# newboard.net
KiCad netlist of a schematic drawn in EAGLE
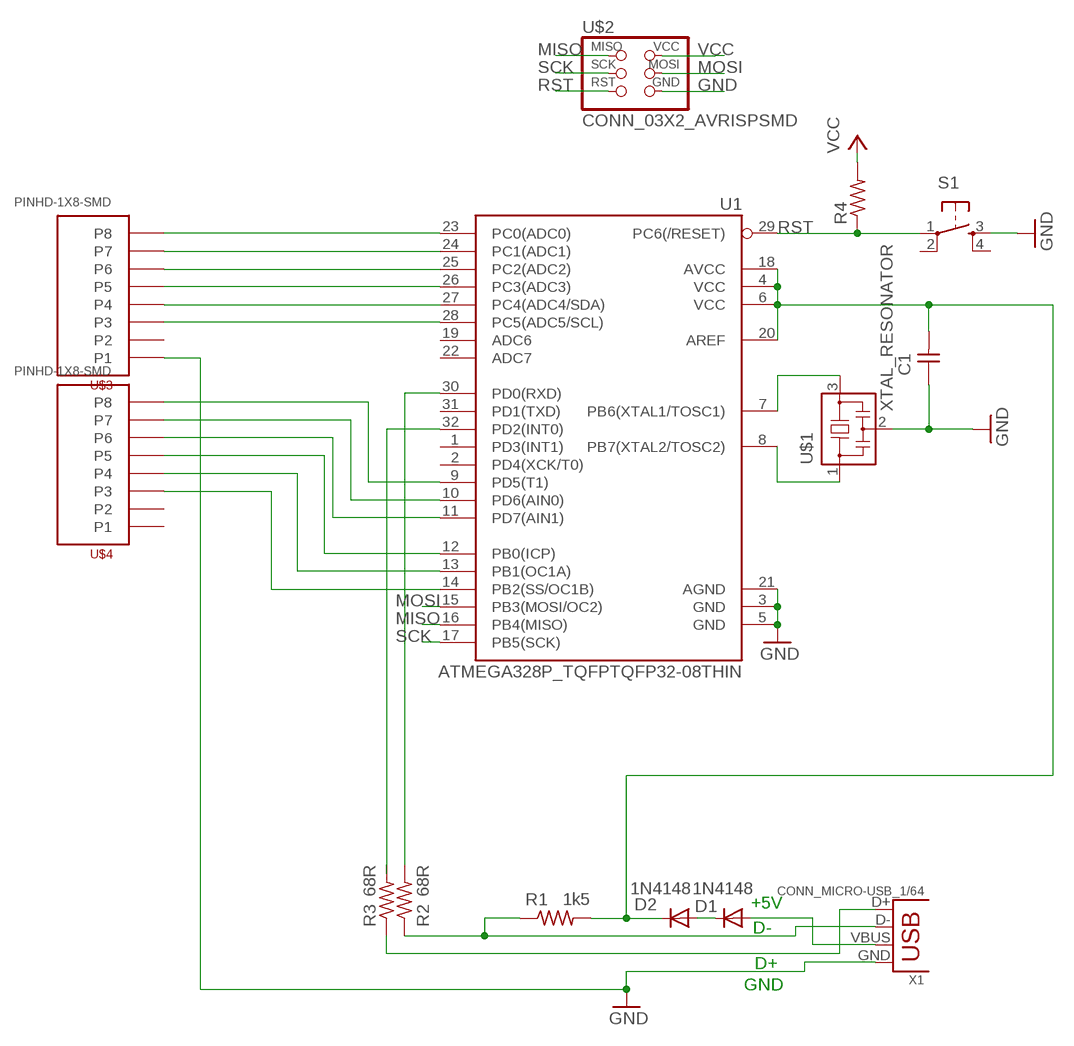
[diagram p0: schematic, sheet 1]

(export (version "E")
  (design (tool "Eeschema 10.0.6"))
  (components
    (comp (ref "C1")
      (value "CAP_UNPOLARIZEDFAB")
      (footprint "eagle-import:C1206FAB")
      (libsource (lib "eagle-import") (part "CAP_UNPOLARIZEDFAB"))
    )
    (comp (ref "D1")
      (value "1N4148")
      (footprint "eagle-import:DO35-10")
      (libsource (lib "eagle-import") (part "1N4148"))
    )
    (comp (ref "D2")
      (value "1N4148")
      (footprint "eagle-import:DO35-10")
      (libsource (lib "eagle-import") (part "1N4148"))
    )
    (comp (ref "R1")
      (value "1k5")
      (footprint "eagle-import:R1206FAB")
      (libsource (lib "eagle-import") (part "R1206FAB"))
    )
    (comp (ref "R2")
      (value "68R")
      (footprint "eagle-import:R1206FAB")
      (libsource (lib "eagle-import") (part "R1206FAB"))
    )
    (comp (ref "R3")
      (value "68R")
      (footprint "eagle-import:R1206FAB")
      (libsource (lib "eagle-import") (part "R1206FAB"))
    )
    (comp (ref "R4")
      (value "R1206FAB")
      (footprint "eagle-import:R1206FAB")
      (libsource (lib "eagle-import") (part "R1206FAB"))
    )
    (comp (ref "S1")
      (value "SW_SWITCH_TACTILE_6MM6MM_SWITCH")
      (footprint "eagle-import:6MM_SWITCH")
      (libsource (lib "eagle-import") (part "SW_SWITCH_TACTILE_6MM6MM_SWITCH"))
    )
    (comp (ref "U$1")
      (value "XTAL_RESONATOR")
      (footprint "eagle-import:EFOBM")
      (libsource (lib "eagle-import") (part "XTAL_RESONATOR"))
    )
    (comp (ref "U$2")
      (value "CONN_03X2_AVRISPSMD")
      (footprint "eagle-import:2X03SMD")
      (libsource (lib "eagle-import") (part "CONN_03X2_AVRISPSMD"))
    )
    (comp (ref "U$3")
      (value "PINHD-1X8-SMD")
      (footprint "eagle-import:1X08SMD")
      (libsource (lib "eagle-import") (part "PINHD-1X8-SMD"))
    )
    (comp (ref "U$4")
      (value "PINHD-1X8-SMD")
      (footprint "eagle-import:1X08SMD")
      (libsource (lib "eagle-import") (part "PINHD-1X8-SMD"))
    )
    (comp (ref "U1")
      (value "ATMEGA328P_TQFPTQFP32-08THIN")
      (footprint "eagle-import:TQFP32-08THIN")
      (libsource (lib "eagle-import") (part "ATMEGA328P_TQFPTQFP32-08THIN"))
    )
    (comp (ref "X1")
      (value "CONN_MICRO-USB_1/64")
      (footprint "eagle-import:DX4R005HJ5_64")
      (libsource (lib "eagle-import") (part "CONN_MICRO-USB_1/64"))
    )
  )
  (nets
    (net (code "1") (name "/MISO") (class "Default")
      (node (ref "U$2") (pin "1") (pinfunction "MISO_1") (pintype "passive"))
      (node (ref "U1") (pin "16") (pinfunction "PB4(MISO)_16") (pintype "bidirectional"))
    )
    (net (code "2") (name "/MOSI") (class "Default")
      (node (ref "U$2") (pin "4") (pinfunction "MOSI_4") (pintype "passive"))
      (node (ref "U1") (pin "15") (pinfunction "PB3(MOSI/OC2)_15") (pintype "bidirectional"))
    )
    (net (code "3") (name "/RST") (class "Default")
      (node (ref "R4") (pin "1") (pinfunction "1_1") (pintype "passive"))
      (node (ref "S1") (pin "1") (pinfunction "P_1") (pintype "passive"))
      (node (ref "U$2") (pin "5") (pinfunction "RST_5") (pintype "passive"))
      (node (ref "U1") (pin "29") (pinfunction "PC6(/RESET)_29") (pintype "bidirectional"))
    )
    (net (code "4") (name "/SCK") (class "Default")
      (node (ref "U$2") (pin "3") (pinfunction "SCK_3") (pintype "passive"))
      (node (ref "U1") (pin "17") (pinfunction "PB5(SCK)_17") (pintype "bidirectional"))
    )
    (net (code "5") (name "GND") (class "Default")
      (node (ref "C1") (pin "1") (pinfunction "1_1") (pintype "passive"))
      (node (ref "S1") (pin "3") (pinfunction "S_3") (pintype "passive"))
      (node (ref "U$1") (pin "2") (pinfunction "2_2") (pintype "passive"))
      (node (ref "U$2") (pin "6") (pinfunction "GND_6") (pintype "passive"))
      (node (ref "U$3") (pin "P1") (pinfunction "P1_P1") (pintype "bidirectional"))
      (node (ref "U1") (pin "21") (pinfunction "AGND_21") (pintype "bidirectional"))
      (node (ref "U1") (pin "3") (pinfunction "GND_3") (pintype "bidirectional"))
      (node (ref "U1") (pin "5") (pinfunction "GND_5") (pintype "bidirectional"))
      (node (ref "X1") (pin "GND") (pinfunction "GND_GND") (pintype "bidirectional"))
    )
    (net (code "6") (name "Net-(D1-PadA)") (class "Default")
      (node (ref "D1") (pin "A") (pinfunction "A_A") (pintype "passive"))
      (node (ref "X1") (pin "VBUS") (pinfunction "VBUS_VBUS") (pintype "bidirectional"))
    )
    (net (code "7") (name "Net-(D1-PadC)") (class "Default")
      (node (ref "D1") (pin "C") (pinfunction "C_C") (pintype "passive"))
      (node (ref "D2") (pin "A") (pinfunction "A_A") (pintype "passive"))
    )
    (net (code "8") (name "Net-(R1-Pad1)") (class "Default")
      (node (ref "R1") (pin "1") (pinfunction "1_1") (pintype "passive"))
      (node (ref "R2") (pin "1") (pinfunction "1_1") (pintype "passive"))
      (node (ref "X1") (pin "D-") (pinfunction "D-_D-") (pintype "bidirectional"))
    )
    (net (code "9") (name "Net-(R3-Pad1)") (class "Default")
      (node (ref "R3") (pin "1") (pinfunction "1_1") (pintype "passive"))
      (node (ref "X1") (pin "D+") (pinfunction "D+_D+") (pintype "bidirectional"))
    )
    (net (code "10") (name "Net-(U1-PB0(ICP))") (class "Default")
      (node (ref "U$4") (pin "P5") (pinfunction "P5_P5") (pintype "bidirectional"))
      (node (ref "U1") (pin "12") (pinfunction "PB0(ICP)_12") (pintype "bidirectional"))
    )
    (net (code "11") (name "Net-(U1-PB1(OC1A))") (class "Default")
      (node (ref "U$4") (pin "P4") (pinfunction "P4_P4") (pintype "bidirectional"))
      (node (ref "U1") (pin "13") (pinfunction "PB1(OC1A)_13") (pintype "bidirectional"))
    )
    (net (code "12") (name "Net-(U1-PB2(SS{slash}OC1B))") (class "Default")
      (node (ref "U$4") (pin "P3") (pinfunction "P3_P3") (pintype "bidirectional"))
      (node (ref "U1") (pin "14") (pinfunction "PB2(SS/OC1B)_14") (pintype "bidirectional"))
    )
    (net (code "13") (name "Net-(U1-PB6(XTAL1{slash}TOSC1))") (class "Default")
      (node (ref "U$1") (pin "3") (pinfunction "3_3") (pintype "passive"))
      (node (ref "U1") (pin "7") (pinfunction "PB6(XTAL1/TOSC1)_7") (pintype "bidirectional"))
    )
    (net (code "14") (name "Net-(U1-PB7(XTAL2{slash}TOSC2))") (class "Default")
      (node (ref "U$1") (pin "1") (pinfunction "1_1") (pintype "passive"))
      (node (ref "U1") (pin "8") (pinfunction "PB7(XTAL2/TOSC2)_8") (pintype "bidirectional"))
    )
    (net (code "15") (name "Net-(U1-PC0(ADC0))") (class "Default")
      (node (ref "U$3") (pin "P8") (pinfunction "P8_P8") (pintype "bidirectional"))
      (node (ref "U1") (pin "23") (pinfunction "PC0(ADC0)_23") (pintype "bidirectional"))
    )
    (net (code "16") (name "Net-(U1-PC1(ADC1))") (class "Default")
      (node (ref "U$3") (pin "P7") (pinfunction "P7_P7") (pintype "bidirectional"))
      (node (ref "U1") (pin "24") (pinfunction "PC1(ADC1)_24") (pintype "bidirectional"))
    )
    (net (code "17") (name "Net-(U1-PC2(ADC2))") (class "Default")
      (node (ref "U$3") (pin "P6") (pinfunction "P6_P6") (pintype "bidirectional"))
      (node (ref "U1") (pin "25") (pinfunction "PC2(ADC2)_25") (pintype "bidirectional"))
    )
    (net (code "18") (name "Net-(U1-PC3(ADC3))") (class "Default")
      (node (ref "U$3") (pin "P5") (pinfunction "P5_P5") (pintype "bidirectional"))
      (node (ref "U1") (pin "26") (pinfunction "PC3(ADC3)_26") (pintype "bidirectional"))
    )
    (net (code "19") (name "Net-(U1-PC4(ADC4{slash}SDA))") (class "Default")
      (node (ref "U$3") (pin "P4") (pinfunction "P4_P4") (pintype "bidirectional"))
      (node (ref "U1") (pin "27") (pinfunction "PC4(ADC4/SDA)_27") (pintype "bidirectional"))
    )
    (net (code "20") (name "Net-(U1-PC5(ADC5{slash}SCL))") (class "Default")
      (node (ref "U$3") (pin "P3") (pinfunction "P3_P3") (pintype "bidirectional"))
      (node (ref "U1") (pin "28") (pinfunction "PC5(ADC5/SCL)_28") (pintype "bidirectional"))
    )
    (net (code "21") (name "Net-(U1-PD0(RXD))") (class "Default")
      (node (ref "R2") (pin "2") (pinfunction "2_2") (pintype "passive"))
      (node (ref "U1") (pin "30") (pinfunction "PD0(RXD)_30") (pintype "bidirectional"))
    )
    (net (code "22") (name "Net-(U1-PD2(INT0))") (class "Default")
      (node (ref "R3") (pin "2") (pinfunction "2_2") (pintype "passive"))
      (node (ref "U1") (pin "32") (pinfunction "PD2(INT0)_32") (pintype "bidirectional"))
    )
    (net (code "23") (name "Net-(U1-PD5(T1))") (class "Default")
      (node (ref "U$4") (pin "P8") (pinfunction "P8_P8") (pintype "bidirectional"))
      (node (ref "U1") (pin "9") (pinfunction "PD5(T1)_9") (pintype "bidirectional"))
    )
    (net (code "24") (name "Net-(U1-PD6(AIN0))") (class "Default")
      (node (ref "U$4") (pin "P7") (pinfunction "P7_P7") (pintype "bidirectional"))
      (node (ref "U1") (pin "10") (pinfunction "PD6(AIN0)_10") (pintype "bidirectional"))
    )
    (net (code "25") (name "Net-(U1-PD7(AIN1))") (class "Default")
      (node (ref "U$4") (pin "P6") (pinfunction "P6_P6") (pintype "bidirectional"))
      (node (ref "U1") (pin "11") (pinfunction "PD7(AIN1)_11") (pintype "bidirectional"))
    )
    (net (code "26") (name "VCC") (class "Default")
      (node (ref "C1") (pin "2") (pinfunction "2_2") (pintype "passive"))
      (node (ref "D2") (pin "C") (pinfunction "C_C") (pintype "passive"))
      (node (ref "R1") (pin "2") (pinfunction "2_2") (pintype "passive"))
      (node (ref "R4") (pin "2") (pinfunction "2_2") (pintype "passive"))
      (node (ref "U$2") (pin "2") (pinfunction "VCC_2") (pintype "passive"))
      (node (ref "U1") (pin "18") (pinfunction "AVCC_18") (pintype "bidirectional"))
      (node (ref "U1") (pin "20") (pinfunction "AREF_20") (pintype "bidirectional"))
      (node (ref "U1") (pin "4") (pinfunction "VCC_4") (pintype "bidirectional"))
      (node (ref "U1") (pin "6") (pinfunction "VCC_6") (pintype "bidirectional"))
    )
    (net (code "27") (name "unconnected-(S1-P1-Pad2)") (class "Default")
      (node (ref "S1") (pin "2") (pinfunction "P1_2") (pintype "passive"))
    )
    (net (code "28") (name "unconnected-(S1-S1-Pad4)") (class "Default")
      (node (ref "S1") (pin "4") (pinfunction "S1_4") (pintype "passive"))
    )
    (net (code "29") (name "unconnected-(U$3-PadP2)") (class "Default")
      (node (ref "U$3") (pin "P2") (pinfunction "P2_P2") (pintype "bidirectional"))
    )
    (net (code "30") (name "unconnected-(U$4-PadP1)") (class "Default")
      (node (ref "U$4") (pin "P1") (pinfunction "P1_P1") (pintype "bidirectional"))
    )
    (net (code "31") (name "unconnected-(U$4-PadP2)") (class "Default")
      (node (ref "U$4") (pin "P2") (pinfunction "P2_P2") (pintype "bidirectional"))
    )
    (net (code "32") (name "unconnected-(U1-ADC6-Pad19)") (class "Default")
      (node (ref "U1") (pin "19") (pinfunction "ADC6_19") (pintype "bidirectional"))
    )
    (net (code "33") (name "unconnected-(U1-ADC7-Pad22)") (class "Default")
      (node (ref "U1") (pin "22") (pinfunction "ADC7_22") (pintype "bidirectional"))
    )
    (net (code "34") (name "unconnected-(U1-PD1(TXD)-Pad31)") (class "Default")
      (node (ref "U1") (pin "31") (pinfunction "PD1(TXD)_31") (pintype "bidirectional"))
    )
    (net (code "35") (name "unconnected-(U1-PD3(INT1)-Pad1)") (class "Default")
      (node (ref "U1") (pin "1") (pinfunction "PD3(INT1)_1") (pintype "bidirectional"))
    )
    (net (code "36") (name "unconnected-(U1-PD4(XCK{slash}T0)-Pad2)") (class "Default")
      (node (ref "U1") (pin "2") (pinfunction "PD4(XCK/T0)_2") (pintype "bidirectional"))
    )
  )
)
